# PLclose.net
KiCad netlist of a schematic drawn in EAGLE
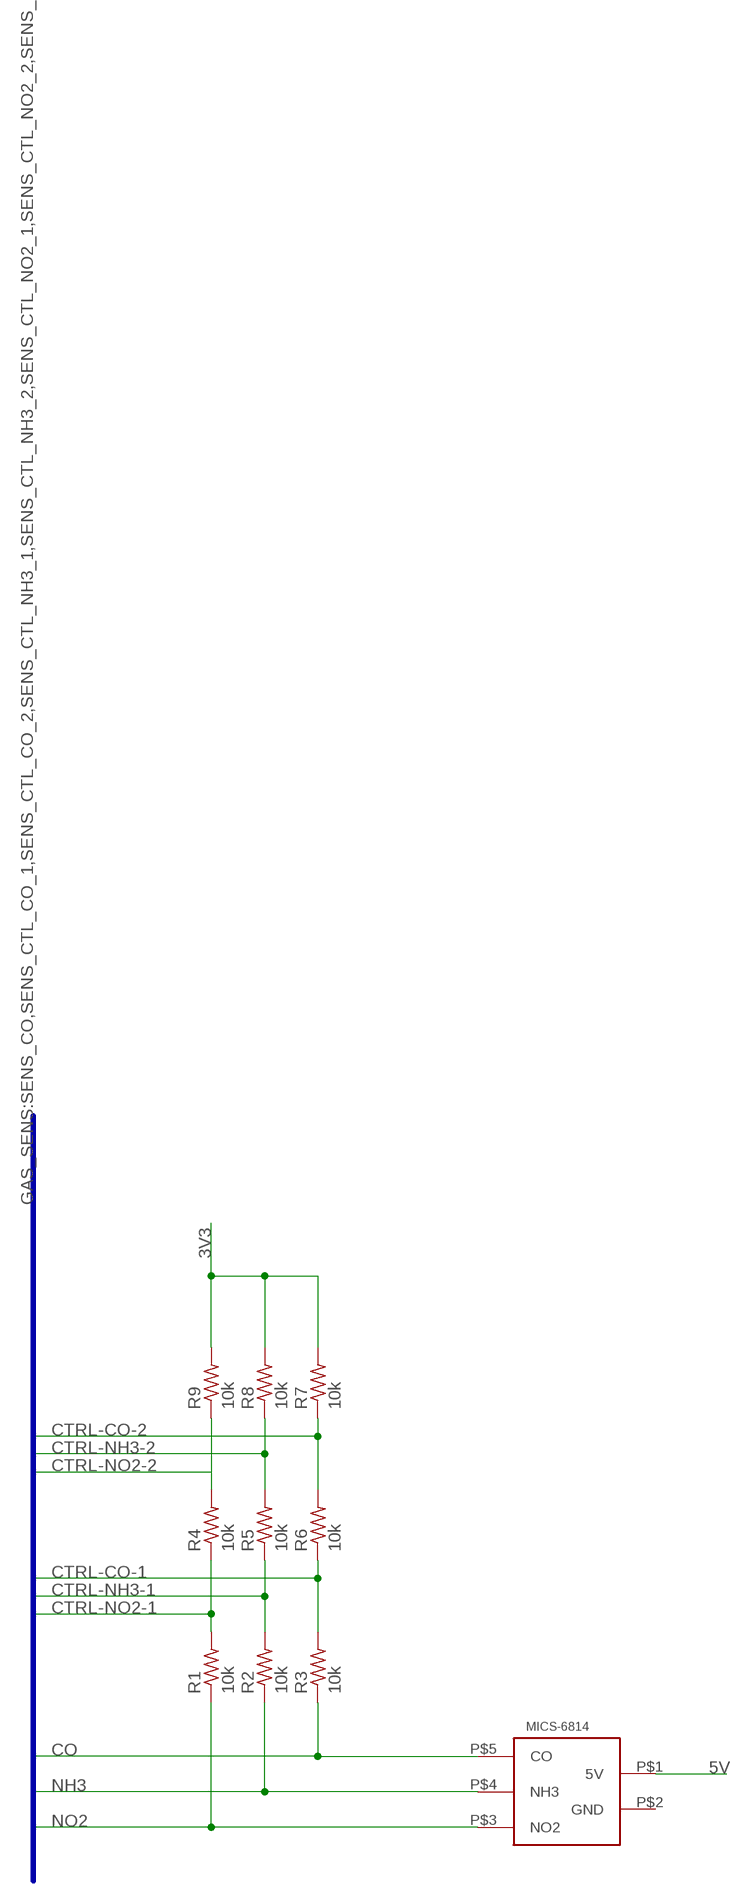
[diagram p0: schematic, sheet 1]

(export (version "E")
  (design (tool "Eeschema 10.0.6"))
  (components
    (comp (ref "MICS-6814")
      (value "MICS-6814")
      (footprint "eagle-import:MICS-6814")
      (libsource (lib "eagle-import") (part "MICS-6814"))
    )
    (comp (ref "R1")
      (value "10k")
      (footprint "eagle-import:R0603")
      (libsource (lib "eagle-import") (part "R-US_R0603"))
    )
    (comp (ref "R2")
      (value "10k")
      (footprint "eagle-import:R0603")
      (libsource (lib "eagle-import") (part "R-US_R0603"))
    )
    (comp (ref "R3")
      (value "10k")
      (footprint "eagle-import:R0603")
      (libsource (lib "eagle-import") (part "R-US_R0603"))
    )
    (comp (ref "R4")
      (value "10k")
      (footprint "eagle-import:R0603")
      (libsource (lib "eagle-import") (part "R-US_R0603"))
    )
    (comp (ref "R5")
      (value "10k")
      (footprint "eagle-import:R0603")
      (libsource (lib "eagle-import") (part "R-US_R0603"))
    )
    (comp (ref "R6")
      (value "10k")
      (footprint "eagle-import:R0603")
      (libsource (lib "eagle-import") (part "R-US_R0603"))
    )
    (comp (ref "R7")
      (value "10k")
      (footprint "eagle-import:R0603")
      (libsource (lib "eagle-import") (part "R-US_R0603"))
    )
    (comp (ref "R8")
      (value "10k")
      (footprint "eagle-import:R0603")
      (libsource (lib "eagle-import") (part "R-US_R0603"))
    )
    (comp (ref "R9")
      (value "10k")
      (footprint "eagle-import:R0603")
      (libsource (lib "eagle-import") (part "R-US_R0603"))
    )
  )
  (nets
    (net (code "10") (name "/3V3") (class "Default")
      (node (ref "R7") (pin "2") (pinfunction "2_2") (pintype "passive"))
      (node (ref "R8") (pin "2") (pinfunction "2_2") (pintype "passive"))
      (node (ref "R9") (pin "2") (pinfunction "2_2") (pintype "passive"))
    )
    (net (code "11") (name "/5V") (class "Default")
      (node (ref "MICS-6814") (pin "P$1") (pinfunction "5V_P$1") (pintype "bidirectional"))
    )
    (net (code "12") (name "/CO") (class "Default")
      (node (ref "MICS-6814") (pin "P$5") (pinfunction "CO_P$5") (pintype "bidirectional"))
      (node (ref "R3") (pin "1") (pinfunction "1_1") (pintype "passive"))
    )
    (net (code "13") (name "/CTRL-CO-1") (class "Default")
      (node (ref "R3") (pin "2") (pinfunction "2_2") (pintype "passive"))
      (node (ref "R6") (pin "1") (pinfunction "1_1") (pintype "passive"))
    )
    (net (code "14") (name "/CTRL-CO-2") (class "Default")
      (node (ref "R6") (pin "2") (pinfunction "2_2") (pintype "passive"))
      (node (ref "R7") (pin "1") (pinfunction "1_1") (pintype "passive"))
    )
    (net (code "15") (name "/CTRL-NH3-1") (class "Default")
      (node (ref "R2") (pin "2") (pinfunction "2_2") (pintype "passive"))
      (node (ref "R5") (pin "1") (pinfunction "1_1") (pintype "passive"))
    )
    (net (code "16") (name "/CTRL-NH3-2") (class "Default")
      (node (ref "R5") (pin "2") (pinfunction "2_2") (pintype "passive"))
      (node (ref "R8") (pin "1") (pinfunction "1_1") (pintype "passive"))
    )
    (net (code "17") (name "/CTRL-NO2-1") (class "Default")
      (node (ref "R1") (pin "2") (pinfunction "2_2") (pintype "passive"))
      (node (ref "R4") (pin "1") (pinfunction "1_1") (pintype "passive"))
    )
    (net (code "18") (name "/CTRL-NO2-2") (class "Default")
      (node (ref "R4") (pin "2") (pinfunction "2_2") (pintype "passive"))
      (node (ref "R9") (pin "1") (pinfunction "1_1") (pintype "passive"))
    )
    (net (code "19") (name "/NH3") (class "Default")
      (node (ref "MICS-6814") (pin "P$4") (pinfunction "NH3_P$4") (pintype "bidirectional"))
      (node (ref "R2") (pin "1") (pinfunction "1_1") (pintype "passive"))
    )
    (net (code "20") (name "/NO2") (class "Default")
      (node (ref "MICS-6814") (pin "P$3") (pinfunction "NO2_P$3") (pintype "bidirectional"))
      (node (ref "R1") (pin "1") (pinfunction "1_1") (pintype "passive"))
    )
    (net (code "22") (name "unconnected-(MICS-6814-GND-PadP$2)") (class "Default")
      (node (ref "MICS-6814") (pin "P$2") (pinfunction "GND_P$2") (pintype "bidirectional"))
    )
  )
)
